# Pixracer_V1_FMU_Alternative_2.net
KiCad netlist of a schematic drawn in Altium Designer
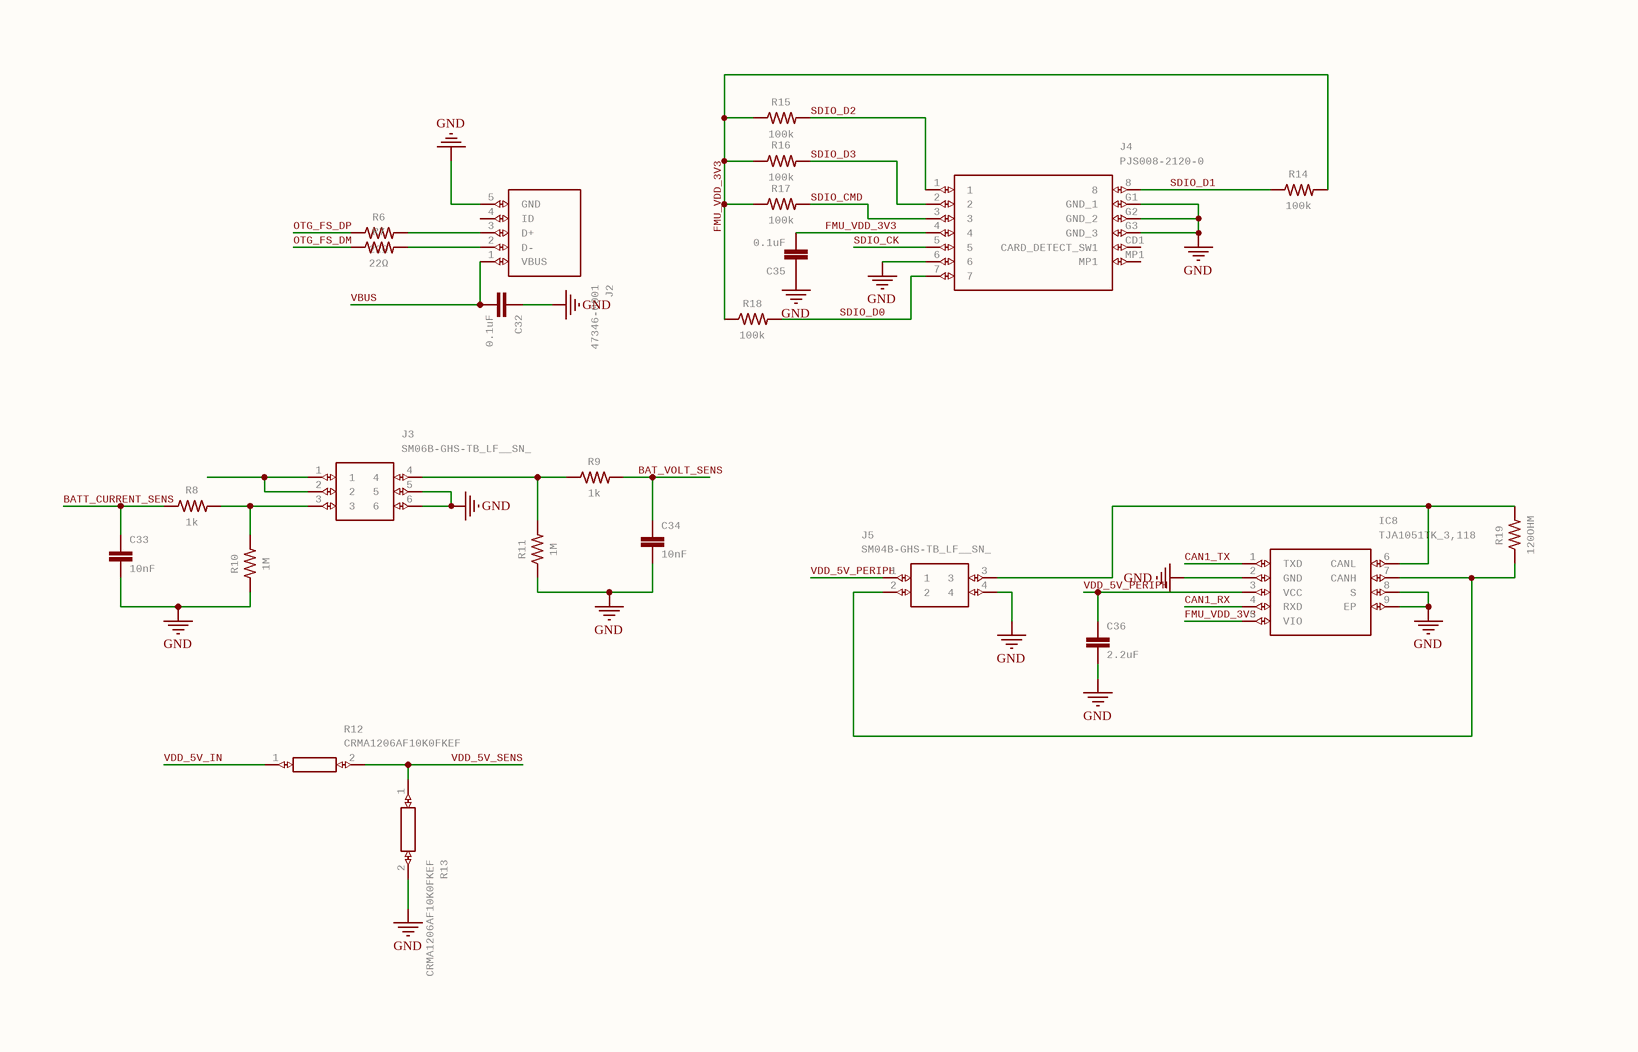
[diagram p0: Pixracer_V1_FMU_Alternative_2.SchDoc]

(export (version "E")
  (design (tool "Eeschema 10.0.6"))
  (components
    (comp (ref "C32")
      (value "0.1uF")
      (footprint "0603")
      (libsource (lib "SparkFun-Capacitors") (part "0.1UF-0603-100V-10%-X7R-WE"))
    )
    (comp (ref "C33")
      (value "10nF")
      (footprint "0603")
      (libsource (lib "SparkFun-Capacitors") (part "10NF-0603-50V-10%"))
    )
    (comp (ref "C34")
      (value "10nF")
      (footprint "0603")
      (libsource (lib "SparkFun-Capacitors") (part "10NF-0603-50V-10%"))
    )
    (comp (ref "C35")
      (value "0.1uF")
      (footprint "0603")
      (libsource (lib "") (part "0.1UF-0603-100V-10%-X7R-WE_1"))
    )
    (comp (ref "C36")
      (value "2.2uF")
      (footprint "1206")
      (libsource (lib "SparkFun-Capacitors") (part "2.2UF-1206-50V-10%"))
    )
    (comp (ref "IC8")
      (value "TJA1051TK_3,118")
      (footprint "SON65P300X300X100-9N")
      (description "High-speed CAN transceiver")
      (fields (field (name "MANUFACTURER_PART_NUMBER") "TJA1051TK/3,118"))
      (libsource (lib "SamacSys_Parts") (part "TJA1051TK_3,118"))
    )
    (comp (ref "J2")
      (value "47346-0001")
      (footprint "47346-0001")
      (fields (field (name "MOUSER_PART_NUMBER") "538-47346-0001"))
      (libsource (lib "SamacSys_Parts") (part "47346-0001"))
    )
    (comp (ref "J3")
      (value "SM06B-GHS-TB_LF__SN_")
      (footprint "SM06B-GHS-TB")
      (fields
        (field (name "MANUFACTURER_PART_NUMBER") "SM06B-GHS-TB(LF)(SN)")
        (field (name "RS_PART_NUMBER") "7521800P")
      )
      (libsource (lib "SamacSys_Parts") (part "SM06B-GHS-TB_LF__SN_"))
    )
    (comp (ref "J4")
      (value "PJS008-2120-0")
      (footprint "PJS00821200")
      (description "Memory Card Connectors STD MNT MICRO SD PUSH-PUSH, SMT CONN")
      (fields (field (name "MOUSER_PART_NUMBER") "945-PJS008-2120-0"))
      (libsource (lib "SamacSys_Parts") (part "PJS008-2120-0"))
    )
    (comp (ref "J5")
      (value "SM04B-GHS-TB_LF__SN_")
      (footprint "SM04B-GHS-TB")
      (description "JST GH Series, 1.25mm Pitch 4 Way Right Angle PCB Header, Solder Termination, 1A")
      (fields
        (field (name "MANUFACTURER_PART_NUMBER") "SM04B-GHS-TB(LF)(SN)")
        (field (name "RS_PART_NUMBER") "7521797P")
      )
      (libsource (lib "SamacSys_Parts") (part "SM04B-GHS-TB_LF__SN_"))
    )
    (comp (ref "R6")
      (value "22Ω")
      (footprint "0603")
      (libsource (lib "SparkFun-Resistors") (part "22OHM-0603-1/10W-1%"))
    )
    (comp (ref "R7")
      (value "22Ω")
      (footprint "0603")
      (libsource (lib "SparkFun-Resistors") (part "22OHM-0603-1/10W-1%"))
    )
    (comp (ref "R8")
      (value "1k")
      (footprint "0603")
      (libsource (lib "SparkFun-Resistors") (part "1KOHM-0603-1/10W-1%"))
    )
    (comp (ref "R9")
      (value "1k")
      (footprint "0603")
      (libsource (lib "SparkFun-Resistors") (part "1KOHM-0603-1/10W-1%"))
    )
    (comp (ref "R10")
      (value "1M")
      (footprint "0603")
      (libsource (lib "SparkFun-Resistors") (part "1MOHM-0603-1/4W-5%"))
    )
    (comp (ref "R11")
      (value "1M")
      (footprint "0603")
      (libsource (lib "SparkFun-Resistors") (part "1MOHM-0603-1/4W-5%"))
    )
    (comp (ref "R12")
      (value "CRMA1206AF10K0FKEF")
      (footprint "RESC3216X74N")
      (description "Thick Film Resistors - SMD 0.30W 10Kohm 1% AEC-Q200")
      (fields (field (name "MOUSER_PART_NUMBER") "71-CRMA1206AF10K0FKF"))
      (libsource (lib "SamacSys_Parts") (part "CRMA1206AF10K0FKEF"))
    )
    (comp (ref "R13")
      (value "CRMA1206AF10K0FKEF")
      (footprint "RESC3216X74N")
      (description "Thick Film Resistors - SMD 0.30W 10Kohm 1% AEC-Q200")
      (fields (field (name "MOUSER_PART_NUMBER") "71-CRMA1206AF10K0FKF"))
      (libsource (lib "SamacSys_Parts") (part "CRMA1206AF10K0FKEF"))
    )
    (comp (ref "R14")
      (value "100k")
      (footprint "0603")
      (libsource (lib "SparkFun-Resistors") (part "100KOHM-0603-1/10W-1%"))
    )
    (comp (ref "R15")
      (value "100k")
      (footprint "0603")
      (libsource (lib "SparkFun-Resistors") (part "100KOHM-0603-1/10W-1%"))
    )
    (comp (ref "R16")
      (value "100k")
      (footprint "0603")
      (libsource (lib "SparkFun-Resistors") (part "100KOHM-0603-1/10W-1%"))
    )
    (comp (ref "R17")
      (value "100k")
      (footprint "0603")
      (libsource (lib "SparkFun-Resistors") (part "100KOHM-0603-1/10W-1%"))
    )
    (comp (ref "R18")
      (value "100k")
      (footprint "0603")
      (libsource (lib "SparkFun-Resistors") (part "100KOHM-0603-1/10W-1%"))
    )
    (comp (ref "R19")
      (value "120OHM")
      (footprint "0603")
      (libsource (lib "SparkFun-Resistors") (part "120OHM"))
    )
  )
  (nets
    (net (code "1") (name "/BATT_CURRENT_SENS") (class "Default")
      (node (ref "C33") (pin "1") (pinfunction "1_1") (pintype "passive"))
      (node (ref "R8") (pin "1") (pinfunction "1_1") (pintype "passive"))
    )
    (net (code "2") (name "/BAT_VOLT_SENS") (class "Default")
      (node (ref "C34") (pin "1") (pinfunction "1_1") (pintype "passive"))
      (node (ref "R9") (pin "2") (pinfunction "2_2") (pintype "passive"))
    )
    (net (code "3") (name "/CAN1_RX") (class "Default")
      (node (ref "IC8") (pin "4") (pinfunction "RXD_4") (pintype "bidirectional"))
    )
    (net (code "4") (name "/CAN1_TX") (class "Default")
      (node (ref "IC8") (pin "1") (pinfunction "TXD_1") (pintype "bidirectional"))
    )
    (net (code "5") (name "/FMU_VDD_3V3") (class "Default")
      (node (ref "C35") (pin "2") (pinfunction "2_2") (pintype "passive"))
      (node (ref "IC8") (pin "5") (pinfunction "VIO_5") (pintype "bidirectional"))
      (node (ref "J4") (pin "4") (pinfunction "4_4") (pintype "bidirectional"))
      (node (ref "R14") (pin "2") (pinfunction "2_2") (pintype "passive"))
      (node (ref "R15") (pin "1") (pinfunction "1_1") (pintype "passive"))
      (node (ref "R16") (pin "1") (pinfunction "1_1") (pintype "passive"))
      (node (ref "R17") (pin "1") (pinfunction "1_1") (pintype "passive"))
      (node (ref "R18") (pin "1") (pinfunction "1_1") (pintype "passive"))
    )
    (net (code "6") (name "/OTG_FS_DM") (class "Default")
      (node (ref "R7") (pin "1") (pinfunction "1_1") (pintype "passive"))
    )
    (net (code "7") (name "/OTG_FS_DP") (class "Default")
      (node (ref "R6") (pin "1") (pinfunction "1_1") (pintype "passive"))
    )
    (net (code "8") (name "/SDIO_CK") (class "Default")
      (node (ref "J4") (pin "5") (pinfunction "5_5") (pintype "bidirectional"))
    )
    (net (code "9") (name "/SDIO_CMD") (class "Default")
      (node (ref "J4") (pin "3") (pinfunction "3_3") (pintype "bidirectional"))
      (node (ref "R17") (pin "2") (pinfunction "2_2") (pintype "passive"))
    )
    (net (code "10") (name "/SDIO_D0") (class "Default")
      (node (ref "J4") (pin "7") (pinfunction "7_7") (pintype "bidirectional"))
      (node (ref "R18") (pin "2") (pinfunction "2_2") (pintype "passive"))
    )
    (net (code "11") (name "/SDIO_D1") (class "Default")
      (node (ref "J4") (pin "8") (pinfunction "8_8") (pintype "bidirectional"))
      (node (ref "R14") (pin "1") (pinfunction "1_1") (pintype "passive"))
    )
    (net (code "12") (name "/SDIO_D2") (class "Default")
      (node (ref "J4") (pin "1") (pinfunction "1_1") (pintype "bidirectional"))
      (node (ref "R15") (pin "2") (pinfunction "2_2") (pintype "passive"))
    )
    (net (code "13") (name "/SDIO_D3") (class "Default")
      (node (ref "J4") (pin "2") (pinfunction "2_2") (pintype "bidirectional"))
      (node (ref "R16") (pin "2") (pinfunction "2_2") (pintype "passive"))
    )
    (net (code "14") (name "/VBUS") (class "Default")
      (node (ref "C32") (pin "2") (pinfunction "2_2") (pintype "passive"))
      (node (ref "J2") (pin "1") (pinfunction "VBUS_1") (pintype "bidirectional"))
    )
    (net (code "15") (name "/VDD_5V_IN") (class "Default")
      (node (ref "R12") (pin "1") (pinfunction "1_1") (pintype "bidirectional"))
    )
    (net (code "16") (name "/VDD_5V_PERIPH") (class "Default")
      (node (ref "C36") (pin "1") (pinfunction "1_1") (pintype "passive"))
      (node (ref "IC8") (pin "3") (pinfunction "VCC_3") (pintype "bidirectional"))
      (node (ref "J5") (pin "1") (pinfunction "1_1") (pintype "bidirectional"))
    )
    (net (code "17") (name "/VDD_5V_SENS") (class "Default")
      (node (ref "R12") (pin "2") (pinfunction "2_2") (pintype "bidirectional"))
      (node (ref "R13") (pin "1") (pinfunction "1_1") (pintype "bidirectional"))
    )
    (net (code "18") (name "GND") (class "Default")
      (node (ref "C32") (pin "1") (pinfunction "1_1") (pintype "passive"))
      (node (ref "C33") (pin "2") (pinfunction "2_2") (pintype "passive"))
      (node (ref "C34") (pin "2") (pinfunction "2_2") (pintype "passive"))
      (node (ref "C35") (pin "1") (pinfunction "1_1") (pintype "passive"))
      (node (ref "C36") (pin "2") (pinfunction "2_2") (pintype "passive"))
      (node (ref "IC8") (pin "2") (pinfunction "GND_2") (pintype "bidirectional"))
      (node (ref "IC8") (pin "8") (pinfunction "S_8") (pintype "bidirectional"))
      (node (ref "IC8") (pin "9") (pinfunction "EP_9") (pintype "bidirectional"))
      (node (ref "J2") (pin "5") (pinfunction "GND_5") (pintype "bidirectional"))
      (node (ref "J3") (pin "5") (pinfunction "5_5") (pintype "bidirectional"))
      (node (ref "J3") (pin "6") (pinfunction "6_6") (pintype "bidirectional"))
      (node (ref "J4") (pin "6") (pinfunction "6_6") (pintype "bidirectional"))
      (node (ref "J4") (pin "G1") (pinfunction "GND_1_G1") (pintype "bidirectional"))
      (node (ref "J4") (pin "G2") (pinfunction "GND_2_G2") (pintype "bidirectional"))
      (node (ref "J4") (pin "G3") (pinfunction "GND_3_G3") (pintype "bidirectional"))
      (node (ref "J5") (pin "4") (pinfunction "4_4") (pintype "bidirectional"))
      (node (ref "R10") (pin "1") (pinfunction "1_1") (pintype "passive"))
      (node (ref "R11") (pin "1") (pinfunction "1_1") (pintype "passive"))
      (node (ref "R13") (pin "2") (pinfunction "2_2") (pintype "bidirectional"))
    )
    (net (code "19") (name "Net-(IC8-CANH)") (class "Default")
      (node (ref "IC8") (pin "7") (pinfunction "CANH_7") (pintype "bidirectional"))
      (node (ref "J5") (pin "2") (pinfunction "2_2") (pintype "bidirectional"))
      (node (ref "R19") (pin "1") (pinfunction "1_1") (pintype "passive"))
    )
    (net (code "20") (name "Net-(IC8-CANL)") (class "Default")
      (node (ref "IC8") (pin "6") (pinfunction "CANL_6") (pintype "bidirectional"))
      (node (ref "J5") (pin "3") (pinfunction "3_3") (pintype "bidirectional"))
      (node (ref "R19") (pin "2") (pinfunction "2_2") (pintype "passive"))
    )
    (net (code "21") (name "Net-(J2-D+)") (class "Default")
      (node (ref "J2") (pin "3") (pinfunction "D+_3") (pintype "bidirectional"))
      (node (ref "R6") (pin "2") (pinfunction "2_2") (pintype "passive"))
    )
    (net (code "22") (name "Net-(J2-D-)") (class "Default")
      (node (ref "J2") (pin "2") (pinfunction "D-_2") (pintype "bidirectional"))
      (node (ref "R7") (pin "2") (pinfunction "2_2") (pintype "passive"))
    )
    (net (code "23") (name "Net-(J3-Pad1)") (class "Default")
      (node (ref "J3") (pin "1") (pinfunction "1_1") (pintype "bidirectional"))
      (node (ref "J3") (pin "2") (pinfunction "2_2") (pintype "bidirectional"))
    )
    (net (code "24") (name "Net-(J3-Pad3)") (class "Default")
      (node (ref "J3") (pin "3") (pinfunction "3_3") (pintype "bidirectional"))
      (node (ref "R10") (pin "2") (pinfunction "2_2") (pintype "passive"))
      (node (ref "R8") (pin "2") (pinfunction "2_2") (pintype "passive"))
    )
    (net (code "25") (name "Net-(J3-Pad4)") (class "Default")
      (node (ref "J3") (pin "4") (pinfunction "4_4") (pintype "bidirectional"))
      (node (ref "R11") (pin "2") (pinfunction "2_2") (pintype "passive"))
      (node (ref "R9") (pin "1") (pinfunction "1_1") (pintype "passive"))
    )
    (net (code "26") (name "unconnected-(J2-ID-Pad4)") (class "Default")
      (node (ref "J2") (pin "4") (pinfunction "ID_4") (pintype "bidirectional"))
    )
    (net (code "27") (name "unconnected-(J4-CARD_DETECT_SW1-PadCD1)") (class "Default")
      (node (ref "J4") (pin "CD1") (pinfunction "CARD_DETECT_SW1_CD1") (pintype "bidirectional"))
    )
    (net (code "28") (name "unconnected-(J4-PadMP1)") (class "Default")
      (node (ref "J4") (pin "MP1") (pinfunction "MP1_MP1") (pintype "bidirectional"))
    )
  )
)
